# Sheet1.net
KiCad netlist of a schematic drawn in Altium Designer
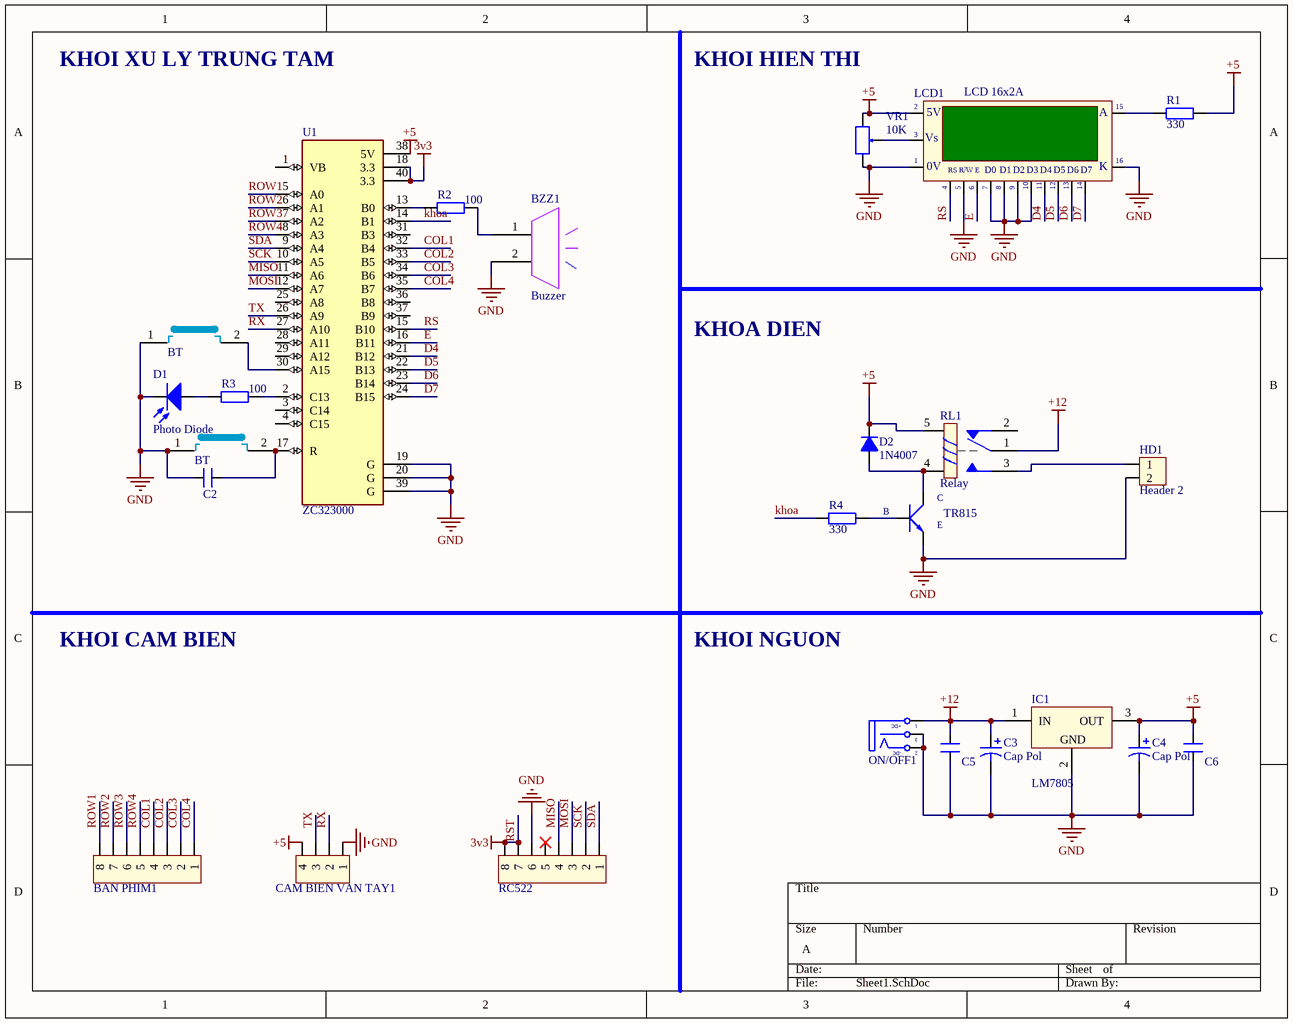
[diagram p0: Sheet1.SchDoc]

(export (version "E")
  (design (tool "Eeschema 10.0.6"))
  (components
    (comp (ref "BAN PHIM1")
      (value "JP8")
      (footprint "CON8")
      (description "Connector 8")
      (libsource (lib "syhaunguyen") (part "Con8"))
    )
    (comp (ref "BT1") (value "BT") (footprint "SW4") (libsource (lib "My library altium") (part "BUTTON")))
    (comp (ref "BT2") (value "BT") (footprint "SW4") (libsource (lib "My library altium") (part "BUTTON")))
    (comp (ref "BZZ1")
      (value "Buzzer")
      (footprint "buzzer 5V")
      (libsource (lib "My library altium") (part "Buzzer"))
    )
    (comp (ref "C2")
      (value "CAP gom")
      (footprint "CN1")
      (libsource (lib "My library altium") (part "CAP gom"))
    )
    (comp (ref "C3")
      (value "Cap Pol")
      (footprint "C3MM")
      (description "Polarized Capacitor (Axial)")
      (fields (field (name "PUBLISHER") "Altium Limited"))
      (libsource (lib "My library altium") (part "Cap Pol"))
    )
    (comp (ref "C4")
      (value "Cap Pol")
      (footprint "C3MM")
      (description "Polarized Capacitor (Axial)")
      (fields (field (name "PUBLISHER") "Altium Limited"))
      (libsource (lib "My library altium") (part "Cap Pol"))
    )
    (comp (ref "C5")
      (value "CAP gom")
      (footprint "CN1")
      (libsource (lib "My library altium") (part "CAP gom"))
    )
    (comp (ref "C6")
      (value "CAP gom")
      (footprint "CN1")
      (libsource (lib "My library altium") (part "CAP gom"))
    )
    (comp (ref "CAM BIEN VAN TAY1")
      (value "JP4")
      (footprint "CON4")
      (description "Connector 4")
      (libsource (lib "syhaunguyen") (part "Con4"))
    )
    (comp (ref "D1")
      (value "Photo Diode")
      (footprint "LED-5")
      (description "Photosensitive Diode")
      (libsource (lib "My library altium") (part "Photo Diode"))
    )
    (comp (ref "D2")
      (value "1N4007")
      (footprint "D1A")
      (description "Diode 1A")
      (libsource (lib "syhaunguyen") (part "D1A"))
    )
    (comp (ref "HD1")
      (value "Header 2")
      (footprint "HED2")
      (description "Header 2 (Green)")
      (libsource (lib "syhaunguyen") (part "Hed2"))
    )
    (comp (ref "IC1")
      (value "LM7805")
      (footprint "QTO-220")
      (description "On ap +, from + 5 to + 24VDC")
      (libsource (lib "My library altium") (part "LM78xx"))
    )
    (comp (ref "LCD1")
      (value "LCD 16x2A")
      (footprint "LCD16X2")
      (description "LCD dipslay 16 char, 2 line")
      (libsource (lib "My Library") (part "LCD16x2A"))
    )
    (comp (ref "ON/OFF1")
      (value "POWER")
      (footprint "DC-IN")
      (libsource (lib "My library altium") (part "DCIN"))
    )
    (comp (ref "R1")
      (value "330")
      (footprint "DIEN TRO 1/4 W")
      (description "Resistor")
      (fields (field (name "PUBLISHER") "Altium Limited"))
      (libsource (lib "My Library") (part "Res 1/4 W"))
    )
    (comp (ref "R2")
      (value "100")
      (footprint "DIEN TRO 1/4 W")
      (description "Resistor")
      (fields (field (name "PUBLISHER") "Altium Limited"))
      (libsource (lib "My Library") (part "Res 1/4 W"))
    )
    (comp (ref "R3")
      (value "100")
      (footprint "DIEN TRO 1/4 W")
      (description "Resistor")
      (fields (field (name "PUBLISHER") "Altium Limited"))
      (libsource (lib "My Library") (part "Res 1/4 W"))
    )
    (comp (ref "R4")
      (value "330")
      (footprint "DIEN TRO 1/4 W")
      (description "Resistor")
      (fields (field (name "PUBLISHER") "Altium Limited"))
      (libsource (lib "My Library") (part "Res 1/4 W"))
    )
    (comp (ref "RC522")
      (value "JP8")
      (footprint "CON8")
      (description "Connector 8")
      (libsource (lib "syhaunguyen") (part "Con8"))
    )
    (comp (ref "RL1")
      (value "Relay")
      (footprint "RL_SPDT_10A")
      (description "Relay SPDT 5 Pin")
      (libsource (lib "My library altium") (part "Relay SRD"))
    )
    (comp (ref "STA.TR1")
      (value "TR815")
      (footprint "QTO-92")
      (description "NPN 600mW, ECB")
      (libsource (lib "My library altium") (part "C1815"))
    )
    (comp (ref "U1")
      (value "ZC323000")
      (footprint "MODULE_ZC323000")
      (description "STM32F103C8T6 ARM STM32 Minimum System Development Board Module For Arduino")
      (fields (field (name "MF") "YKS"))
      (libsource (lib "stm32 blue pill") (part "ZC323000"))
    )
    (comp (ref "VR1")
      (value "10K")
      (footprint "VR")
      (description "Var Resistor")
      (libsource (lib "My Library") (part "VR"))
    )
  )
  (nets
    (net (code "1") (name "+5") (class "Default")
      (node (ref "C4") (pin "1") (pinfunction "1_1") (pintype "passive"))
      (node (ref "C6") (pin "2") (pinfunction "2_2") (pintype "passive"))
      (node (ref "CAM BIEN VAN TAY1") (pin "4") (pinfunction "4_4") (pintype "passive"))
      (node (ref "D2") (pin "2") (pinfunction "K_2") (pintype "passive"))
      (node (ref "IC1") (pin "3") (pinfunction "OUT_3") (pintype "passive"))
      (node (ref "LCD1") (pin "2") (pinfunction "VDD_2") (pintype "passive"))
      (node (ref "R1") (pin "2") (pinfunction "2_2") (pintype "passive"))
      (node (ref "RL1") (pin "5") (pinfunction "5_5") (pintype "passive"))
      (node (ref "U1") (pin "38") (pinfunction "5V_38") (pintype "power_in"))
      (node (ref "VR1") (pin "1") (pinfunction "1_1") (pintype "passive"))
    )
    (net (code "2") (name "+12") (class "Default")
      (node (ref "C3") (pin "1") (pinfunction "1_1") (pintype "passive"))
      (node (ref "C5") (pin "2") (pinfunction "2_2") (pintype "passive"))
      (node (ref "IC1") (pin "1") (pinfunction "IN_1") (pintype "passive"))
      (node (ref "ON/OFF1") (pin "1") (pinfunction "T_1") (pintype "passive"))
      (node (ref "RL1") (pin "1") (pinfunction "1_1") (pintype "passive"))
    )
    (net (code "3") (name "/COL1") (class "Default")
      (node (ref "BAN PHIM1") (pin "4") (pinfunction "4_4") (pintype "passive"))
      (node (ref "U1") (pin "32") (pinfunction "B4_32") (pintype "bidirectional"))
    )
    (net (code "4") (name "/COL2") (class "Default")
      (node (ref "BAN PHIM1") (pin "3") (pinfunction "3_3") (pintype "passive"))
      (node (ref "U1") (pin "33") (pinfunction "B5_33") (pintype "bidirectional"))
    )
    (net (code "5") (name "/COL3") (class "Default")
      (node (ref "BAN PHIM1") (pin "2") (pinfunction "2_2") (pintype "passive"))
      (node (ref "U1") (pin "34") (pinfunction "B6_34") (pintype "bidirectional"))
    )
    (net (code "6") (name "/COL4") (class "Default")
      (node (ref "BAN PHIM1") (pin "1") (pinfunction "1_1") (pintype "passive"))
      (node (ref "U1") (pin "35") (pinfunction "B7_35") (pintype "bidirectional"))
    )
    (net (code "7") (name "/D4") (class "Default")
      (node (ref "LCD1") (pin "11") (pinfunction "D4_11") (pintype "passive"))
      (node (ref "U1") (pin "21") (pinfunction "B12_21") (pintype "bidirectional"))
    )
    (net (code "8") (name "/D5") (class "Default")
      (node (ref "LCD1") (pin "12") (pinfunction "D5_12") (pintype "passive"))
      (node (ref "U1") (pin "22") (pinfunction "B13_22") (pintype "bidirectional"))
    )
    (net (code "9") (name "/D6") (class "Default")
      (node (ref "LCD1") (pin "13") (pinfunction "D6_13") (pintype "passive"))
      (node (ref "U1") (pin "23") (pinfunction "B14_23") (pintype "bidirectional"))
    )
    (net (code "10") (name "/D7") (class "Default")
      (node (ref "LCD1") (pin "14") (pinfunction "D7_14") (pintype "passive"))
      (node (ref "U1") (pin "24") (pinfunction "B15_24") (pintype "bidirectional"))
    )
    (net (code "11") (name "/E") (class "Default")
      (node (ref "LCD1") (pin "6") (pinfunction "~{EN}_6") (pintype "passive"))
      (node (ref "U1") (pin "16") (pinfunction "B11_16") (pintype "bidirectional"))
    )
    (net (code "12") (name "/MISO") (class "Default")
      (node (ref "RC522") (pin "4") (pinfunction "4_4") (pintype "passive"))
      (node (ref "U1") (pin "11") (pinfunction "A6_11") (pintype "bidirectional"))
    )
    (net (code "13") (name "/MOSI") (class "Default")
      (node (ref "RC522") (pin "3") (pinfunction "3_3") (pintype "passive"))
      (node (ref "U1") (pin "12") (pinfunction "A7_12") (pintype "bidirectional"))
    )
    (net (code "14") (name "/ROW1") (class "Default")
      (node (ref "BAN PHIM1") (pin "8") (pinfunction "8_8") (pintype "passive"))
      (node (ref "U1") (pin "5") (pinfunction "A0_5") (pintype "bidirectional"))
    )
    (net (code "15") (name "/ROW2") (class "Default")
      (node (ref "BAN PHIM1") (pin "7") (pinfunction "7_7") (pintype "passive"))
      (node (ref "U1") (pin "6") (pinfunction "A1_6") (pintype "bidirectional"))
    )
    (net (code "16") (name "/ROW3") (class "Default")
      (node (ref "BAN PHIM1") (pin "6") (pinfunction "6_6") (pintype "passive"))
      (node (ref "U1") (pin "7") (pinfunction "A2_7") (pintype "bidirectional"))
    )
    (net (code "17") (name "/ROW4") (class "Default")
      (node (ref "BAN PHIM1") (pin "5") (pinfunction "5_5") (pintype "passive"))
      (node (ref "U1") (pin "8") (pinfunction "A3_8") (pintype "bidirectional"))
    )
    (net (code "18") (name "/RS") (class "Default")
      (node (ref "LCD1") (pin "4") (pinfunction "RS_4") (pintype "passive"))
      (node (ref "U1") (pin "15") (pinfunction "B10_15") (pintype "bidirectional"))
    )
    (net (code "19") (name "/RX") (class "Default")
      (node (ref "CAM BIEN VAN TAY1") (pin "2") (pinfunction "2_2") (pintype "passive"))
      (node (ref "U1") (pin "27") (pinfunction "A10_27") (pintype "bidirectional"))
    )
    (net (code "20") (name "/SCK") (class "Default")
      (node (ref "RC522") (pin "2") (pinfunction "2_2") (pintype "passive"))
      (node (ref "U1") (pin "10") (pinfunction "A5_10") (pintype "bidirectional"))
    )
    (net (code "21") (name "/SDA") (class "Default")
      (node (ref "RC522") (pin "1") (pinfunction "1_1") (pintype "passive"))
      (node (ref "U1") (pin "9") (pinfunction "A4_9") (pintype "bidirectional"))
    )
    (net (code "22") (name "/TX") (class "Default")
      (node (ref "CAM BIEN VAN TAY1") (pin "3") (pinfunction "3_3") (pintype "passive"))
      (node (ref "U1") (pin "26") (pinfunction "A9_26") (pintype "bidirectional"))
    )
    (net (code "23") (name "/khoa") (class "Default")
      (node (ref "R4") (pin "1") (pinfunction "1_1") (pintype "passive"))
      (node (ref "U1") (pin "14") (pinfunction "B1_14") (pintype "bidirectional"))
    )
    (net (code "24") (name "3v3") (class "Default")
      (node (ref "RC522") (pin "7") (pinfunction "7_7") (pintype "passive"))
      (node (ref "RC522") (pin "8") (pinfunction "8_8") (pintype "passive"))
      (node (ref "U1") (pin "18") (pinfunction "3.3_18") (pintype "power_in"))
      (node (ref "U1") (pin "40") (pinfunction "3.3_40") (pintype "power_in"))
    )
    (net (code "25") (name "GND") (class "Default")
      (node (ref "BT1") (pin "1") (pinfunction "1_1") (pintype "passive"))
      (node (ref "BT2") (pin "1") (pinfunction "1_1") (pintype "passive"))
      (node (ref "BZZ1") (pin "2") (pinfunction "2_2") (pintype "passive"))
      (node (ref "C2") (pin "1") (pinfunction "1_1") (pintype "passive"))
      (node (ref "C3") (pin "2") (pinfunction "2_2") (pintype "passive"))
      (node (ref "C4") (pin "2") (pinfunction "2_2") (pintype "passive"))
      (node (ref "C5") (pin "1") (pinfunction "1_1") (pintype "passive"))
      (node (ref "C6") (pin "1") (pinfunction "1_1") (pintype "passive"))
      (node (ref "CAM BIEN VAN TAY1") (pin "1") (pinfunction "1_1") (pintype "passive"))
      (node (ref "D1") (pin "2") (pinfunction "K_2") (pintype "passive"))
      (node (ref "HD1") (pin "2") (pinfunction "2_2") (pintype "passive"))
      (node (ref "IC1") (pin "2") (pinfunction "GND_2") (pintype "passive"))
      (node (ref "LCD1") (pin "1") (pinfunction "GND_1") (pintype "passive"))
      (node (ref "LCD1") (pin "10") (pinfunction "D3_10") (pintype "passive"))
      (node (ref "LCD1") (pin "16") (pinfunction "K_16") (pintype "passive"))
      (node (ref "LCD1") (pin "5") (pinfunction "R/~{W}_5") (pintype "passive"))
      (node (ref "LCD1") (pin "7") (pinfunction "D0_7") (pintype "passive"))
      (node (ref "LCD1") (pin "8") (pinfunction "D1_8") (pintype "passive"))
      (node (ref "LCD1") (pin "9") (pinfunction "D2_9") (pintype "passive"))
      (node (ref "ON/OFF1") (pin "2") (pinfunction "TN_2") (pintype "passive"))
      (node (ref "ON/OFF1") (pin "3") (pinfunction "S_3") (pintype "power_in"))
      (node (ref "RC522") (pin "6") (pinfunction "6_6") (pintype "passive"))
      (node (ref "STA.TR1") (pin "1") (pinfunction "E_1") (pintype "passive"))
      (node (ref "U1") (pin "19") (pinfunction "G_19") (pintype "power_in"))
      (node (ref "U1") (pin "20") (pinfunction "G_20") (pintype "power_in"))
      (node (ref "U1") (pin "39") (pinfunction "G_39") (pintype "power_in"))
      (node (ref "VR1") (pin "3") (pinfunction "3_3") (pintype "passive"))
    )
    (net (code "26") (name "Net-(BZZ1-Pad1)") (class "Default")
      (node (ref "BZZ1") (pin "1") (pinfunction "1_1") (pintype "passive"))
      (node (ref "R2") (pin "2") (pinfunction "2_2") (pintype "passive"))
    )
    (net (code "27") (name "Net-(D1-A)") (class "Default")
      (node (ref "D1") (pin "1") (pinfunction "A_1") (pintype "passive"))
      (node (ref "R3") (pin "1") (pinfunction "1_1") (pintype "passive"))
    )
    (net (code "28") (name "Net-(D2-A)") (class "Default")
      (node (ref "D2") (pin "1") (pinfunction "A_1") (pintype "passive"))
      (node (ref "RL1") (pin "4") (pinfunction "4_4") (pintype "passive"))
      (node (ref "STA.TR1") (pin "2") (pinfunction "C_2") (pintype "passive"))
    )
    (net (code "29") (name "Net-(HD1-Pad1)") (class "Default")
      (node (ref "HD1") (pin "1") (pinfunction "1_1") (pintype "passive"))
      (node (ref "RL1") (pin "3") (pinfunction "3_3") (pintype "passive"))
    )
    (net (code "30") (name "Net-(LCD1-A)") (class "Default")
      (node (ref "LCD1") (pin "15") (pinfunction "A_15") (pintype "passive"))
      (node (ref "R1") (pin "1") (pinfunction "1_1") (pintype "passive"))
    )
    (net (code "31") (name "Net-(LCD1-VEE)") (class "Default")
      (node (ref "LCD1") (pin "3") (pinfunction "VEE_3") (pintype "passive"))
      (node (ref "VR1") (pin "2") (pinfunction "2_2") (pintype "passive"))
    )
    (net (code "32") (name "Net-(STA.TR1-B)") (class "Default")
      (node (ref "R4") (pin "2") (pinfunction "2_2") (pintype "passive"))
      (node (ref "STA.TR1") (pin "3") (pinfunction "B_3") (pintype "passive"))
    )
    (net (code "33") (name "Net-(U1-A15)") (class "Default")
      (node (ref "BT1") (pin "2") (pinfunction "2_2") (pintype "passive"))
      (node (ref "U1") (pin "30") (pinfunction "A15_30") (pintype "bidirectional"))
    )
    (net (code "34") (name "Net-(U1-B0)") (class "Default")
      (node (ref "R2") (pin "1") (pinfunction "1_1") (pintype "passive"))
      (node (ref "U1") (pin "13") (pinfunction "B0_13") (pintype "bidirectional"))
    )
    (net (code "35") (name "Net-(U1-C13)") (class "Default")
      (node (ref "R3") (pin "2") (pinfunction "2_2") (pintype "passive"))
      (node (ref "U1") (pin "2") (pinfunction "C13_2") (pintype "bidirectional"))
    )
    (net (code "36") (name "Net-(U1-R)") (class "Default")
      (node (ref "BT2") (pin "2") (pinfunction "2_2") (pintype "passive"))
      (node (ref "C2") (pin "2") (pinfunction "2_2") (pintype "passive"))
      (node (ref "U1") (pin "17") (pinfunction "R_17") (pintype "bidirectional"))
    )
    (net (code "37") (name "unconnected-(RC522-Pad5)") (class "Default")
      (node (ref "RC522") (pin "5") (pinfunction "5_5") (pintype "passive+no_connect"))
    )
    (net (code "38") (name "unconnected-(RL1-Pad2)") (class "Default")
      (node (ref "RL1") (pin "2") (pinfunction "2_2") (pintype "passive"))
    )
    (net (code "39") (name "unconnected-(U1-A8-Pad25)") (class "Default")
      (node (ref "U1") (pin "25") (pinfunction "A8_25") (pintype "bidirectional"))
    )
    (net (code "40") (name "unconnected-(U1-A11-Pad28)") (class "Default")
      (node (ref "U1") (pin "28") (pinfunction "A11_28") (pintype "bidirectional"))
    )
    (net (code "41") (name "unconnected-(U1-A12-Pad29)") (class "Default")
      (node (ref "U1") (pin "29") (pinfunction "A12_29") (pintype "bidirectional"))
    )
    (net (code "42") (name "unconnected-(U1-B3-Pad31)") (class "Default")
      (node (ref "U1") (pin "31") (pinfunction "B3_31") (pintype "bidirectional"))
    )
    (net (code "43") (name "unconnected-(U1-B8-Pad36)") (class "Default")
      (node (ref "U1") (pin "36") (pinfunction "B8_36") (pintype "bidirectional"))
    )
    (net (code "44") (name "unconnected-(U1-B9-Pad37)") (class "Default")
      (node (ref "U1") (pin "37") (pinfunction "B9_37") (pintype "bidirectional"))
    )
    (net (code "45") (name "unconnected-(U1-C14-Pad3)") (class "Default")
      (node (ref "U1") (pin "3") (pinfunction "C14_3") (pintype "bidirectional"))
    )
    (net (code "46") (name "unconnected-(U1-C15-Pad4)") (class "Default")
      (node (ref "U1") (pin "4") (pinfunction "C15_4") (pintype "bidirectional"))
    )
    (net (code "47") (name "unconnected-(U1-VB-Pad1)") (class "Default")
      (node (ref "U1") (pin "1") (pinfunction "VB_1") (pintype "bidirectional"))
    )
  )
)
